# fpc_cable_all.net
KiCad netlist of a schematic drawn in EAGLE
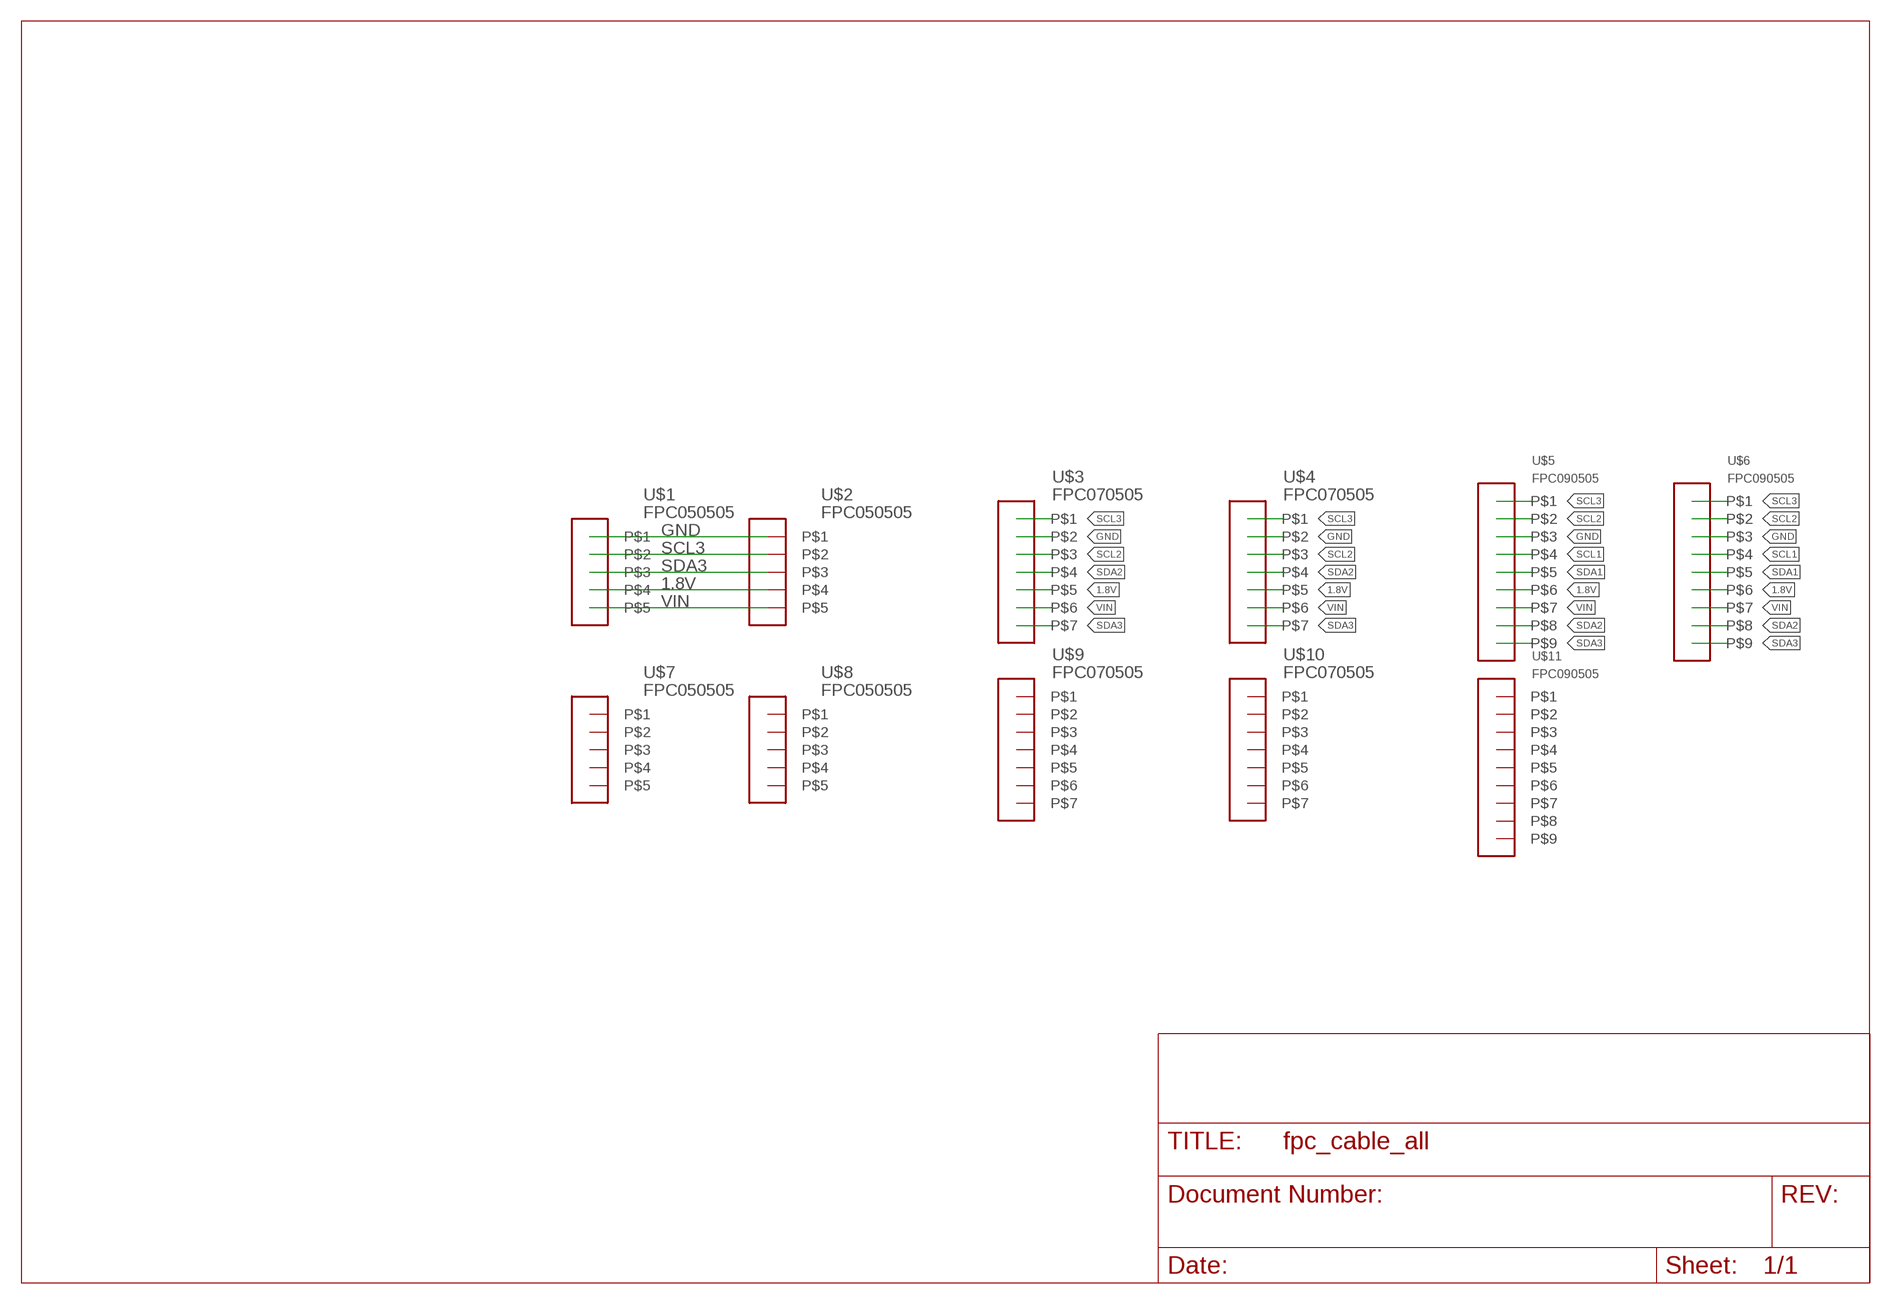
[diagram p0: schematic, sheet 1]

(export (version "E")
  (design (tool "Eeschema 10.0.6"))
  (components
    (comp (ref "U$1")
      (value "FPC050505")
      (footprint "eagle-import:FPC0505")
      (libsource (lib "eagle-import") (part "FPC050505"))
    )
    (comp (ref "U$2")
      (value "FPC050505")
      (footprint "eagle-import:FPC0505")
      (libsource (lib "eagle-import") (part "FPC050505"))
    )
    (comp (ref "U$3")
      (value "FPC070505")
      (footprint "eagle-import:FPC0705")
      (libsource (lib "eagle-import") (part "FPC070505"))
    )
    (comp (ref "U$4")
      (value "FPC070505")
      (footprint "eagle-import:FPC0705")
      (libsource (lib "eagle-import") (part "FPC070505"))
    )
    (comp (ref "U$5")
      (value "FPC090505")
      (footprint "eagle-import:FPC0905")
      (libsource (lib "eagle-import") (part "FPC090505"))
    )
    (comp (ref "U$6")
      (value "FPC090505")
      (footprint "eagle-import:FPC0905")
      (libsource (lib "eagle-import") (part "FPC090505"))
    )
    (comp (ref "U$7")
      (value "FPC050505")
      (footprint "eagle-import:FPC0505")
      (libsource (lib "eagle-import") (part "FPC050505"))
    )
    (comp (ref "U$8")
      (value "FPC050505")
      (footprint "eagle-import:FPC0505")
      (libsource (lib "eagle-import") (part "FPC050505"))
    )
    (comp (ref "U$9")
      (value "FPC070505")
      (footprint "eagle-import:FPC0705")
      (libsource (lib "eagle-import") (part "FPC070505"))
    )
    (comp (ref "U$10")
      (value "FPC070505")
      (footprint "eagle-import:FPC0705")
      (libsource (lib "eagle-import") (part "FPC070505"))
    )
    (comp (ref "U$11")
      (value "FPC090505")
      (footprint "eagle-import:FPC0905")
      (libsource (lib "eagle-import") (part "FPC090505"))
    )
  )
  (nets
    (net (code "1") (name "1.8V") (class "Default")
      (node (ref "U$1") (pin "P$4") (pinfunction "P$4_P$4") (pintype "bidirectional"))
      (node (ref "U$2") (pin "P$4") (pinfunction "P$4_P$4") (pintype "bidirectional"))
      (node (ref "U$3") (pin "P$5") (pinfunction "P$5_P$5") (pintype "bidirectional"))
      (node (ref "U$4") (pin "P$5") (pinfunction "P$5_P$5") (pintype "bidirectional"))
      (node (ref "U$5") (pin "P$6") (pinfunction "P$6_P$6") (pintype "bidirectional"))
      (node (ref "U$6") (pin "P$6") (pinfunction "P$6_P$6") (pintype "bidirectional"))
    )
    (net (code "2") (name "GND") (class "Default")
      (node (ref "U$1") (pin "P$1") (pinfunction "P$1_P$1") (pintype "bidirectional"))
      (node (ref "U$2") (pin "P$1") (pinfunction "P$1_P$1") (pintype "bidirectional"))
      (node (ref "U$3") (pin "P$2") (pinfunction "P$2_P$2") (pintype "bidirectional"))
      (node (ref "U$4") (pin "P$2") (pinfunction "P$2_P$2") (pintype "bidirectional"))
      (node (ref "U$5") (pin "P$3") (pinfunction "P$3_P$3") (pintype "bidirectional"))
      (node (ref "U$6") (pin "P$3") (pinfunction "P$3_P$3") (pintype "bidirectional"))
    )
    (net (code "3") (name "SCL1") (class "Default")
      (node (ref "U$5") (pin "P$4") (pinfunction "P$4_P$4") (pintype "bidirectional"))
      (node (ref "U$6") (pin "P$4") (pinfunction "P$4_P$4") (pintype "bidirectional"))
    )
    (net (code "4") (name "SCL2") (class "Default")
      (node (ref "U$3") (pin "P$3") (pinfunction "P$3_P$3") (pintype "bidirectional"))
      (node (ref "U$4") (pin "P$3") (pinfunction "P$3_P$3") (pintype "bidirectional"))
      (node (ref "U$5") (pin "P$2") (pinfunction "P$2_P$2") (pintype "bidirectional"))
      (node (ref "U$6") (pin "P$2") (pinfunction "P$2_P$2") (pintype "bidirectional"))
    )
    (net (code "5") (name "SCL3") (class "Default")
      (node (ref "U$1") (pin "P$2") (pinfunction "P$2_P$2") (pintype "bidirectional"))
      (node (ref "U$2") (pin "P$2") (pinfunction "P$2_P$2") (pintype "bidirectional"))
      (node (ref "U$3") (pin "P$1") (pinfunction "P$1_P$1") (pintype "bidirectional"))
      (node (ref "U$4") (pin "P$1") (pinfunction "P$1_P$1") (pintype "bidirectional"))
      (node (ref "U$5") (pin "P$1") (pinfunction "P$1_P$1") (pintype "bidirectional"))
      (node (ref "U$6") (pin "P$1") (pinfunction "P$1_P$1") (pintype "bidirectional"))
    )
    (net (code "6") (name "SDA1") (class "Default")
      (node (ref "U$5") (pin "P$5") (pinfunction "P$5_P$5") (pintype "bidirectional"))
      (node (ref "U$6") (pin "P$5") (pinfunction "P$5_P$5") (pintype "bidirectional"))
    )
    (net (code "7") (name "SDA2") (class "Default")
      (node (ref "U$3") (pin "P$4") (pinfunction "P$4_P$4") (pintype "bidirectional"))
      (node (ref "U$4") (pin "P$4") (pinfunction "P$4_P$4") (pintype "bidirectional"))
      (node (ref "U$5") (pin "P$8") (pinfunction "P$8_P$8") (pintype "bidirectional"))
      (node (ref "U$6") (pin "P$8") (pinfunction "P$8_P$8") (pintype "bidirectional"))
    )
    (net (code "8") (name "SDA3") (class "Default")
      (node (ref "U$1") (pin "P$3") (pinfunction "P$3_P$3") (pintype "bidirectional"))
      (node (ref "U$2") (pin "P$3") (pinfunction "P$3_P$3") (pintype "bidirectional"))
      (node (ref "U$3") (pin "P$7") (pinfunction "P$7_P$7") (pintype "bidirectional"))
      (node (ref "U$4") (pin "P$7") (pinfunction "P$7_P$7") (pintype "bidirectional"))
      (node (ref "U$5") (pin "P$9") (pinfunction "P$9_P$9") (pintype "bidirectional"))
      (node (ref "U$6") (pin "P$9") (pinfunction "P$9_P$9") (pintype "bidirectional"))
    )
    (net (code "9") (name "VIN") (class "Default")
      (node (ref "U$1") (pin "P$5") (pinfunction "P$5_P$5") (pintype "bidirectional"))
      (node (ref "U$2") (pin "P$5") (pinfunction "P$5_P$5") (pintype "bidirectional"))
      (node (ref "U$3") (pin "P$6") (pinfunction "P$6_P$6") (pintype "bidirectional"))
      (node (ref "U$4") (pin "P$6") (pinfunction "P$6_P$6") (pintype "bidirectional"))
      (node (ref "U$5") (pin "P$7") (pinfunction "P$7_P$7") (pintype "bidirectional"))
      (node (ref "U$6") (pin "P$7") (pinfunction "P$7_P$7") (pintype "bidirectional"))
    )
    (net (code "10") (name "unconnected-(U$7-PadP$1)") (class "Default")
      (node (ref "U$7") (pin "P$1") (pinfunction "P$1_P$1") (pintype "bidirectional"))
    )
    (net (code "11") (name "unconnected-(U$7-PadP$2)") (class "Default")
      (node (ref "U$7") (pin "P$2") (pinfunction "P$2_P$2") (pintype "bidirectional"))
    )
    (net (code "12") (name "unconnected-(U$7-PadP$3)") (class "Default")
      (node (ref "U$7") (pin "P$3") (pinfunction "P$3_P$3") (pintype "bidirectional"))
    )
    (net (code "13") (name "unconnected-(U$7-PadP$4)") (class "Default")
      (node (ref "U$7") (pin "P$4") (pinfunction "P$4_P$4") (pintype "bidirectional"))
    )
    (net (code "14") (name "unconnected-(U$7-PadP$5)") (class "Default")
      (node (ref "U$7") (pin "P$5") (pinfunction "P$5_P$5") (pintype "bidirectional"))
    )
    (net (code "15") (name "unconnected-(U$8-PadP$1)") (class "Default")
      (node (ref "U$8") (pin "P$1") (pinfunction "P$1_P$1") (pintype "bidirectional"))
    )
    (net (code "16") (name "unconnected-(U$8-PadP$2)") (class "Default")
      (node (ref "U$8") (pin "P$2") (pinfunction "P$2_P$2") (pintype "bidirectional"))
    )
    (net (code "17") (name "unconnected-(U$8-PadP$3)") (class "Default")
      (node (ref "U$8") (pin "P$3") (pinfunction "P$3_P$3") (pintype "bidirectional"))
    )
    (net (code "18") (name "unconnected-(U$8-PadP$4)") (class "Default")
      (node (ref "U$8") (pin "P$4") (pinfunction "P$4_P$4") (pintype "bidirectional"))
    )
    (net (code "19") (name "unconnected-(U$8-PadP$5)") (class "Default")
      (node (ref "U$8") (pin "P$5") (pinfunction "P$5_P$5") (pintype "bidirectional"))
    )
    (net (code "20") (name "unconnected-(U$9-PadP$1)") (class "Default")
      (node (ref "U$9") (pin "P$1") (pinfunction "P$1_P$1") (pintype "bidirectional"))
    )
    (net (code "21") (name "unconnected-(U$9-PadP$2)") (class "Default")
      (node (ref "U$9") (pin "P$2") (pinfunction "P$2_P$2") (pintype "bidirectional"))
    )
    (net (code "22") (name "unconnected-(U$9-PadP$3)") (class "Default")
      (node (ref "U$9") (pin "P$3") (pinfunction "P$3_P$3") (pintype "bidirectional"))
    )
    (net (code "23") (name "unconnected-(U$9-PadP$4)") (class "Default")
      (node (ref "U$9") (pin "P$4") (pinfunction "P$4_P$4") (pintype "bidirectional"))
    )
    (net (code "24") (name "unconnected-(U$9-PadP$5)") (class "Default")
      (node (ref "U$9") (pin "P$5") (pinfunction "P$5_P$5") (pintype "bidirectional"))
    )
    (net (code "25") (name "unconnected-(U$9-PadP$6)") (class "Default")
      (node (ref "U$9") (pin "P$6") (pinfunction "P$6_P$6") (pintype "bidirectional"))
    )
    (net (code "26") (name "unconnected-(U$9-PadP$7)") (class "Default")
      (node (ref "U$9") (pin "P$7") (pinfunction "P$7_P$7") (pintype "bidirectional"))
    )
    (net (code "27") (name "unconnected-(U$10-PadP$1)") (class "Default")
      (node (ref "U$10") (pin "P$1") (pinfunction "P$1_P$1") (pintype "bidirectional"))
    )
    (net (code "28") (name "unconnected-(U$10-PadP$2)") (class "Default")
      (node (ref "U$10") (pin "P$2") (pinfunction "P$2_P$2") (pintype "bidirectional"))
    )
    (net (code "29") (name "unconnected-(U$10-PadP$3)") (class "Default")
      (node (ref "U$10") (pin "P$3") (pinfunction "P$3_P$3") (pintype "bidirectional"))
    )
    (net (code "30") (name "unconnected-(U$10-PadP$4)") (class "Default")
      (node (ref "U$10") (pin "P$4") (pinfunction "P$4_P$4") (pintype "bidirectional"))
    )
    (net (code "31") (name "unconnected-(U$10-PadP$5)") (class "Default")
      (node (ref "U$10") (pin "P$5") (pinfunction "P$5_P$5") (pintype "bidirectional"))
    )
    (net (code "32") (name "unconnected-(U$10-PadP$6)") (class "Default")
      (node (ref "U$10") (pin "P$6") (pinfunction "P$6_P$6") (pintype "bidirectional"))
    )
    (net (code "33") (name "unconnected-(U$10-PadP$7)") (class "Default")
      (node (ref "U$10") (pin "P$7") (pinfunction "P$7_P$7") (pintype "bidirectional"))
    )
    (net (code "34") (name "unconnected-(U$11-PadP$1)") (class "Default")
      (node (ref "U$11") (pin "P$1") (pinfunction "P$1_P$1") (pintype "bidirectional"))
    )
    (net (code "35") (name "unconnected-(U$11-PadP$2)") (class "Default")
      (node (ref "U$11") (pin "P$2") (pinfunction "P$2_P$2") (pintype "bidirectional"))
    )
    (net (code "36") (name "unconnected-(U$11-PadP$3)") (class "Default")
      (node (ref "U$11") (pin "P$3") (pinfunction "P$3_P$3") (pintype "bidirectional"))
    )
    (net (code "37") (name "unconnected-(U$11-PadP$4)") (class "Default")
      (node (ref "U$11") (pin "P$4") (pinfunction "P$4_P$4") (pintype "bidirectional"))
    )
    (net (code "38") (name "unconnected-(U$11-PadP$5)") (class "Default")
      (node (ref "U$11") (pin "P$5") (pinfunction "P$5_P$5") (pintype "bidirectional"))
    )
    (net (code "39") (name "unconnected-(U$11-PadP$6)") (class "Default")
      (node (ref "U$11") (pin "P$6") (pinfunction "P$6_P$6") (pintype "bidirectional"))
    )
    (net (code "40") (name "unconnected-(U$11-PadP$7)") (class "Default")
      (node (ref "U$11") (pin "P$7") (pinfunction "P$7_P$7") (pintype "bidirectional"))
    )
    (net (code "41") (name "unconnected-(U$11-PadP$8)") (class "Default")
      (node (ref "U$11") (pin "P$8") (pinfunction "P$8_P$8") (pintype "bidirectional"))
    )
    (net (code "42") (name "unconnected-(U$11-PadP$9)") (class "Default")
      (node (ref "U$11") (pin "P$9") (pinfunction "P$9_P$9") (pintype "bidirectional"))
    )
  )
)
